# Protection_channel_C_Page_4.net
KiCad netlist of a schematic drawn in Altium Designer
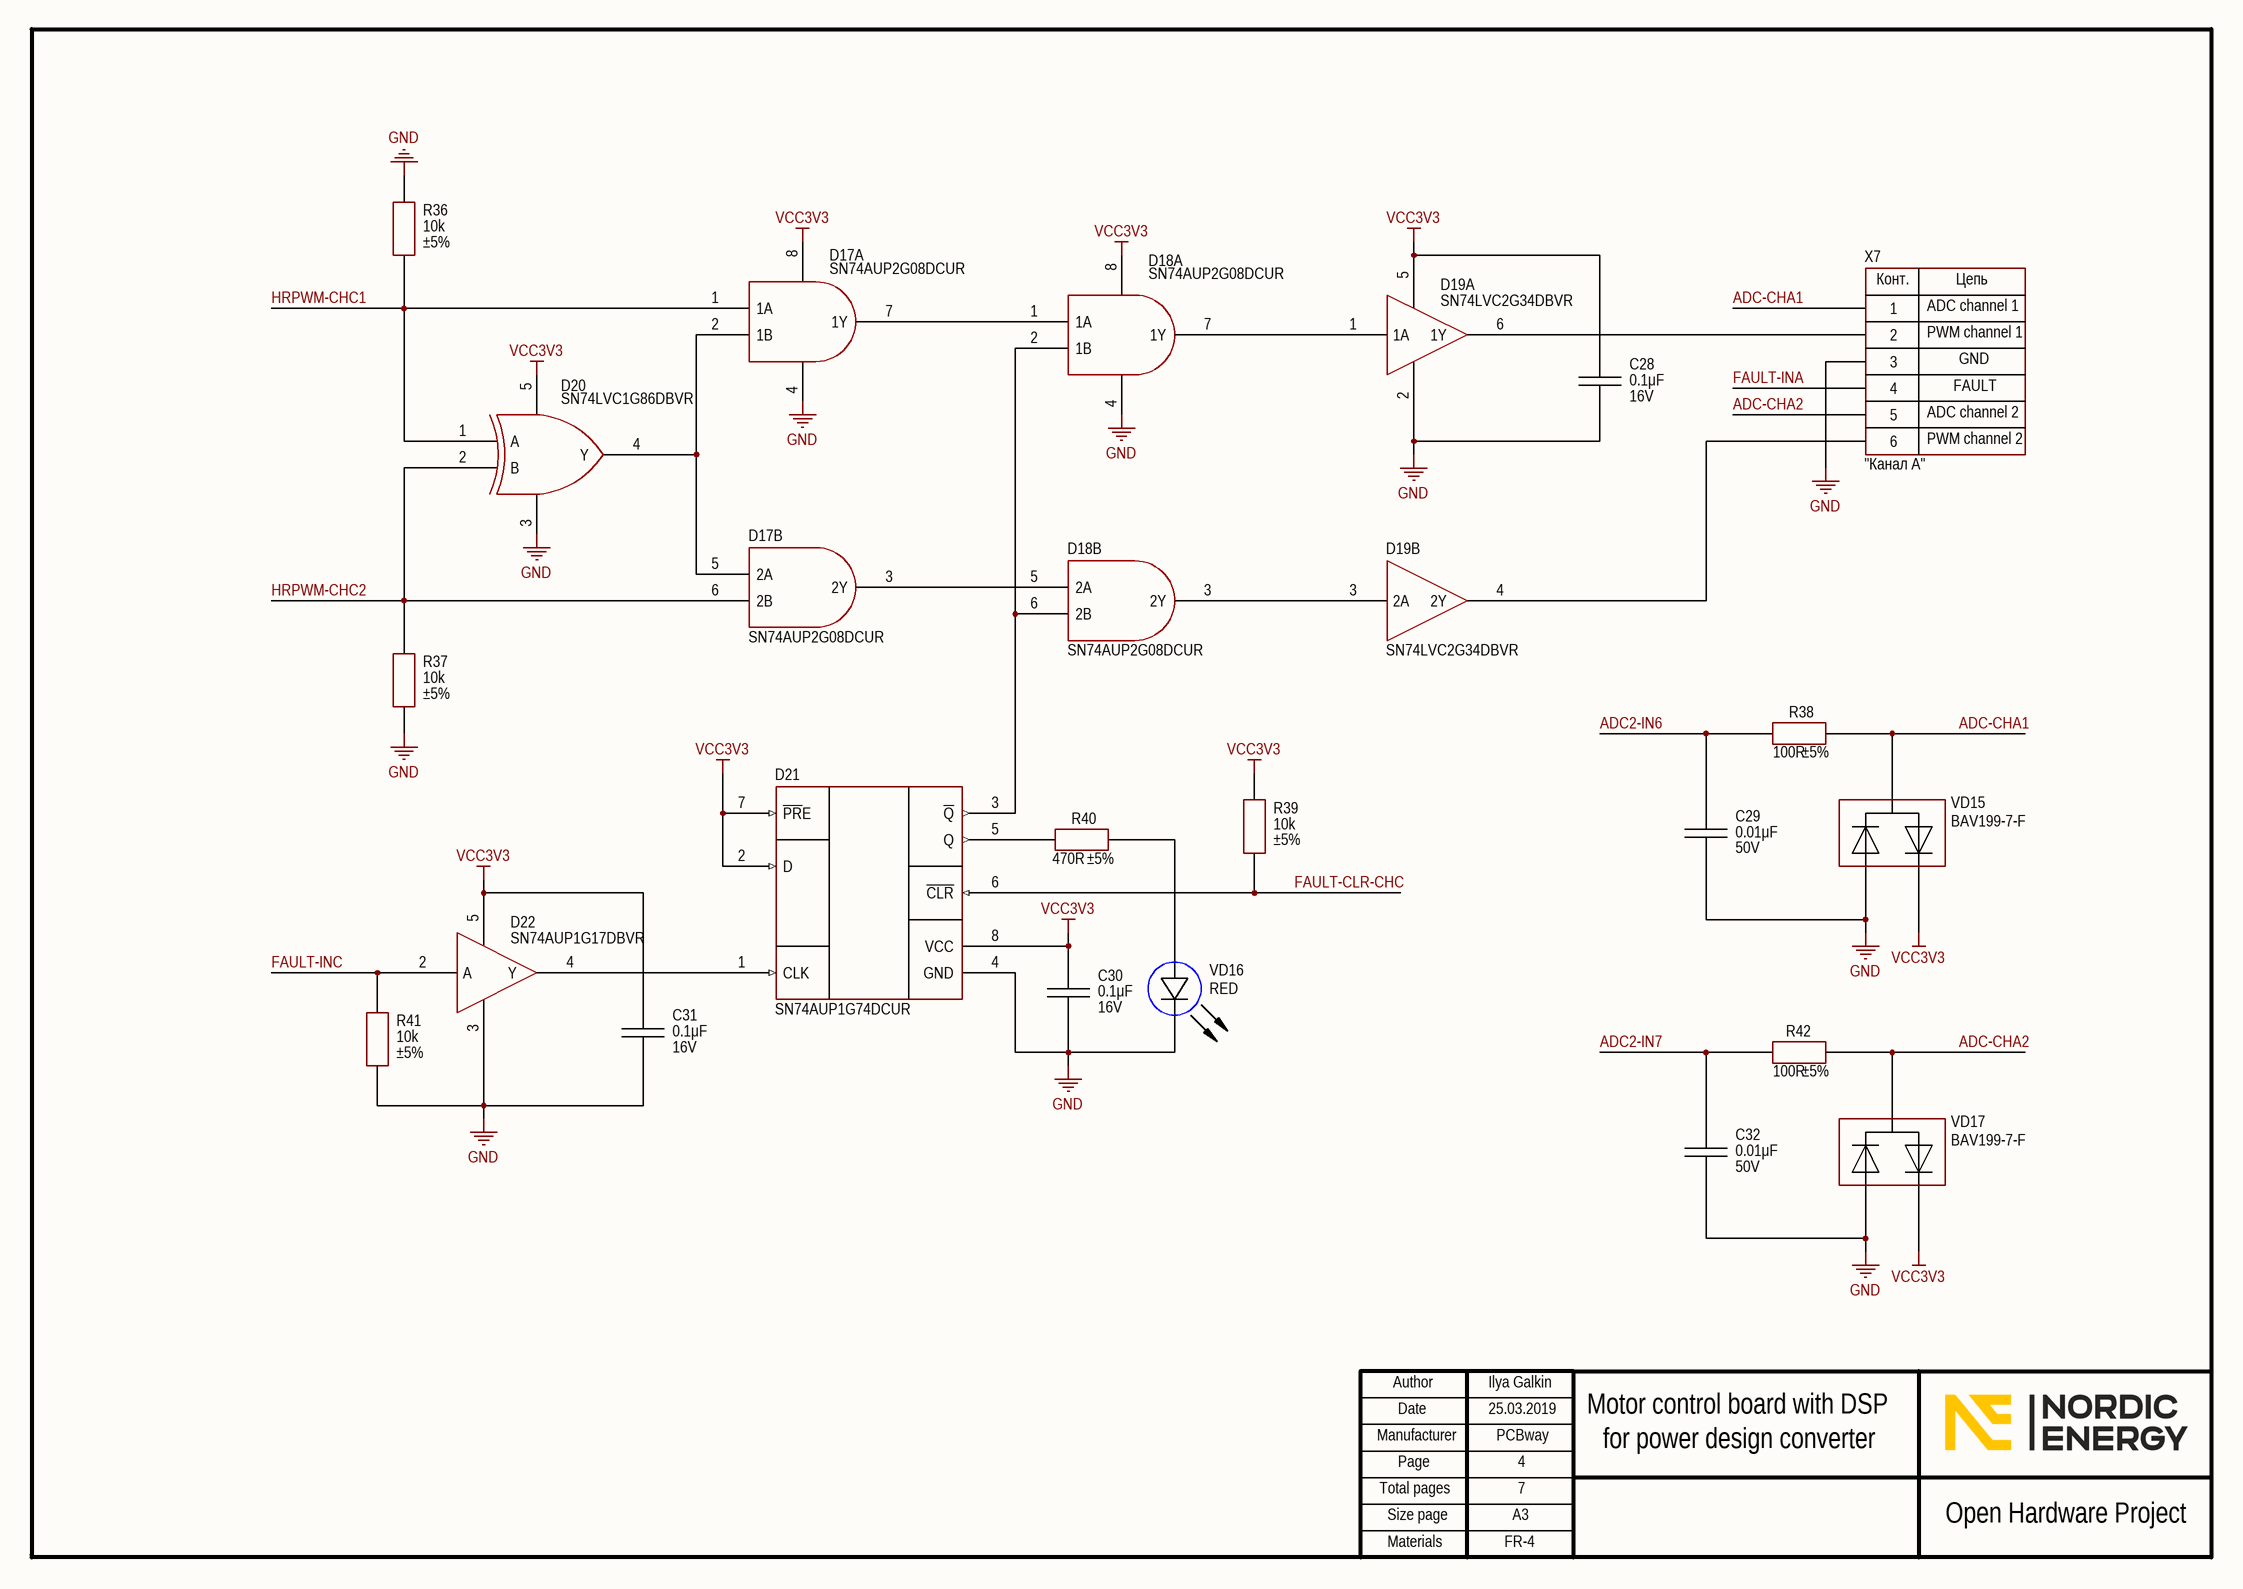
[diagram p0: Protection channel C. Page 4.SchDoc]

(export (version "E")
  (design (tool "Eeschema 10.0.6"))
  (components
    (comp (ref "C28")
      (value "0.1μF")
      (footprint "CAP: 0805")
      (fields
        (field (name "MANUFACTURER") "Yageo")
        (field (name "PARTNUMBER") "CC0805KRX7R7BB104")
        (field (name "VALUEMANUFACTURERPARTNUMBER") "Ceramic capacitor, 0.1μF, X7R, ±10%, 16V, 0805, -55...+125°C")
        (field (name "VOLTAGE") "16V")
      )
      (libsource (lib "Capacitor") (part "Ceramic_0805"))
    )
    (comp (ref "C29")
      (value "0.01μF")
      (footprint "CAP: 0805")
      (fields
        (field (name "MANUFACTURER") "Yageo")
        (field (name "PARTNUMBER") "CC0805KRX7R9BB103")
        (field (name "VALUEMANUFACTURERPARTNUMBER") "Ceramic capacitor, 0.01μF, X7R, ±10%, 50V, 0805, -55...+125°C")
        (field (name "VOLTAGE") "50V")
      )
      (libsource (lib "Capacitor") (part "Ceramic_0805"))
    )
    (comp (ref "C30")
      (value "0.1μF")
      (footprint "CAP: 0805")
      (fields
        (field (name "MANUFACTURER") "Yageo")
        (field (name "PARTNUMBER") "CC0805KRX7R7BB104")
        (field (name "VALUEMANUFACTURERPARTNUMBER") "Ceramic capacitor, 0.1μF, X7R, ±10%, 16V, 0805, -55...+125°C")
        (field (name "VOLTAGE") "16V")
      )
      (libsource (lib "Capacitor") (part "Ceramic_0805"))
    )
    (comp (ref "C31")
      (value "0.1μF")
      (footprint "CAP: 0805")
      (fields
        (field (name "MANUFACTURER") "Yageo")
        (field (name "PARTNUMBER") "CC0805KRX7R7BB104")
        (field (name "VALUEMANUFACTURERPARTNUMBER") "Ceramic capacitor, 0.1μF, X7R, ±10%, 16V, 0805, -55...+125°C")
        (field (name "VOLTAGE") "16V")
      )
      (libsource (lib "Capacitor") (part "Ceramic_0805"))
    )
    (comp (ref "C32")
      (value "0.01μF")
      (footprint "CAP: 0805")
      (fields
        (field (name "MANUFACTURER") "Yageo")
        (field (name "PARTNUMBER") "CC0805KRX7R9BB103")
        (field (name "VALUEMANUFACTURERPARTNUMBER") "Ceramic capacitor, 0.01μF, X7R, ±10%, 50V, 0805, -55...+125°C")
        (field (name "VOLTAGE") "50V")
      )
      (libsource (lib "Capacitor") (part "Ceramic_0805"))
    )
    (comp (ref "D17")
      (value "~")
      (footprint "8-VSSOP")
      (description "AND")
      (fields
        (field (name "MANUFACTURER") "Texas Instruments")
        (field (name "VALUEMANUFACTURERPARTNUMBER") "IC logic AND, 0.8...3.6V, -40...+855°C, 8-VSSOP")
        (field (name "PARTNUMBER") "SN74AUP2G08DCUR")
      )
      (libsource (lib "IC. Logic") (part "SN74AUP2G08DCUR"))
    )
    (comp (ref "D18")
      (value "~")
      (footprint "8-VSSOP")
      (description "AND")
      (fields
        (field (name "MANUFACTURER") "Texas Instruments")
        (field (name "VALUEMANUFACTURERPARTNUMBER") "IC logic AND, 0.8...3.6V, -40...+855°C, 8-VSSOP")
        (field (name "PARTNUMBER") "SN74AUP2G08DCUR")
      )
      (libsource (lib "IC. Logic") (part "SN74AUP2G08DCUR"))
    )
    (comp (ref "D19")
      (value "~")
      (footprint "SOT23-6")
      (description "Buffer")
      (fields
        (field (name "MANUFACTURER") "Texas Instruments")
        (field (name "VALUEMANUFACTURERPARTNUMBER") "IC logic buffer, 1.65...5.5V, -40...+125°C, SOT23-6")
        (field (name "PARTNUMBER") "SN74LVC2G34DBVR")
      )
      (libsource (lib "IC. Logic") (part "SN74LVC2G34DBVR"))
    )
    (comp (ref "D20")
      (value "~")
      (footprint "SOT23-5")
      (description "XOR")
      (fields
        (field (name "MANUFACTURER") "Texas Instruments")
        (field (name "VALUEMANUFACTURERPARTNUMBER") "IC logic XOR, 1.65...5.5V, -40...+125°C, SOT23-5")
        (field (name "PARTNUMBER") "SN74LVC1G86DBVR")
      )
      (libsource (lib "IC. Logic") (part "SN74LVC1G86DBVR"))
    )
    (comp (ref "D21")
      (value "~")
      (footprint "8-VSSOP")
      (description "D-trigger")
      (fields
        (field (name "MANUFACTURER") "Texas Instruments")
        (field (name "VALUEMANUFACTURERPARTNUMBER") "ICtrigger D-type, 0.8...3.6V, -40...+85°C, 8-VSSOP")
        (field (name "PARTNUMBER") "SN74AUP1G74DCUR")
      )
      (libsource (lib "IC. Logic") (part "SN74AUP1G74DCUR"))
    )
    (comp (ref "D22")
      (value "~")
      (footprint "SOT23-5")
      (description "Schmitt trigger")
      (fields
        (field (name "MANUFACTURER") "Texas Instruments")
        (field (name "VALUEMANUFACTURERPARTNUMBER") "IC Schmitt trigger, 0.8...3.6V, -40...+85°C, SOT23-6")
        (field (name "PARTNUMBER") "SN74AUP1G17DBVR")
      )
      (libsource (lib "IC. Logic") (part "SN74AUP1G17DBVR"))
    )
    (comp (ref "R36")
      (value "10k")
      (footprint "RES: 0805")
      (fields
        (field (name "MANUFACTURER") "Yageo")
        (field (name "PARTNUMBER") "RC0805JR-0710KL")
        (field (name "VALUEMANUFACTURERPARTNUMBER") "Resistor film, 10k, ±5%, 0805, 0.125W, -55...+125°C")
        (field (name "TOLERANCE") "±5%")
      )
      (libsource (lib "Resistor") (part "Resistor_0805"))
    )
    (comp (ref "R37")
      (value "10k")
      (footprint "RES: 0805")
      (fields
        (field (name "MANUFACTURER") "Yageo")
        (field (name "PARTNUMBER") "RC0805JR-0710KL")
        (field (name "VALUEMANUFACTURERPARTNUMBER") "Resistor film, 10k, ±5%, 0805, 0.125W, -55...+125°C")
        (field (name "TOLERANCE") "±5%")
      )
      (libsource (lib "Resistor") (part "Resistor_0805"))
    )
    (comp (ref "R38")
      (value "100R")
      (footprint "RES: 0805")
      (fields
        (field (name "MANUFACTURER") "Yageo")
        (field (name "PARTNUMBER") "RC0805JR-07100RL")
        (field (name "VALUEMANUFACTURERPARTNUMBER") "Resistor film, 100R, ±5%, 0805, 0.125W, -55...+125°C")
        (field (name "TOLERANCE") "±5%")
      )
      (libsource (lib "") (part "Resistor_0805_1"))
    )
    (comp (ref "R39")
      (value "10k")
      (footprint "RES: 0805")
      (fields
        (field (name "MANUFACTURER") "Yageo")
        (field (name "PARTNUMBER") "RC0805JR-0710KL")
        (field (name "VALUEMANUFACTURERPARTNUMBER") "Resistor film, 10k, ±5%, 0805, 0.125W, -55...+125°C")
        (field (name "TOLERANCE") "±5%")
      )
      (libsource (lib "Resistor") (part "Resistor_0805"))
    )
    (comp (ref "R40")
      (value "470R")
      (footprint "RES: 0805")
      (fields
        (field (name "MANUFACTURER") "Yageo")
        (field (name "PARTNUMBER") "RC0805JR-07470RL")
        (field (name "VALUEMANUFACTURERPARTNUMBER") "Resistor film, 470R, ±5%, 0805, 0.125W, -55...+125°C")
        (field (name "TOLERANCE") "±5%")
      )
      (libsource (lib "") (part "Resistor_0805_2"))
    )
    (comp (ref "R41")
      (value "10k")
      (footprint "RES: 0805")
      (fields
        (field (name "MANUFACTURER") "Yageo")
        (field (name "PARTNUMBER") "RC0805JR-0710KL")
        (field (name "VALUEMANUFACTURERPARTNUMBER") "Resistor film, 10k, ±5%, 0805, 0.125W, -55...+125°C")
        (field (name "TOLERANCE") "±5%")
      )
      (libsource (lib "Resistor") (part "Resistor_0805"))
    )
    (comp (ref "R42")
      (value "100R")
      (footprint "RES: 0805")
      (fields
        (field (name "MANUFACTURER") "Yageo")
        (field (name "PARTNUMBER") "RC0805JR-07100RL")
        (field (name "VALUEMANUFACTURERPARTNUMBER") "Resistor film, 100R, ±5%, 0805, 0.125W, -55...+125°C")
        (field (name "TOLERANCE") "±5%")
      )
      (libsource (lib "") (part "Resistor_0805_1"))
    )
    (comp (ref "VD15")
      (value "~")
      (footprint "SOT23")
      (fields
        (field (name "MANUFACTURER") "Diodes Incorporated")
        (field (name "VALUEMANUFACTURERPARTNUMBER") "Diode array, 85V, 140mA, 1.1V, 3us, SOT-23, -65...+150°C")
        (field (name "VOLTAGE") "85V")
        (field (name "PARTNUMBER") "BAV199-7-F")
      )
      (libsource (lib "Diode") (part "Diode_array"))
    )
    (comp (ref "VD16")
      (value "~")
      (footprint "LED: 0805R")
      (fields
        (field (name "MANUFACTURER") "Wurth")
        (field (name "VALUEMANUFACTURERPARTNUMBER") "LED, 20mA, 2V, 0805, -55...+150°C")
        (field (name "PARTNUMBER") "150080RS75000")
        (field (name "COLOR") "RED")
      )
      (libsource (lib "Diode") (part "LED_single"))
    )
    (comp (ref "VD17")
      (value "~")
      (footprint "SOT23")
      (fields
        (field (name "MANUFACTURER") "Diodes Incorporated")
        (field (name "VALUEMANUFACTURERPARTNUMBER") "Diode array, 85V, 140mA, 1.1V, 3us, SOT-23, -65...+150°C")
        (field (name "VOLTAGE") "85V")
        (field (name "PARTNUMBER") "BAV199-7-F")
      )
      (libsource (lib "Diode") (part "Diode_array"))
    )
    (comp (ref "X7")
      (value "~")
      (footprint "CON: PLD-6")
      (fields
        (field (name "MANUFACTURER") "Connfly")
        (field (name "VALUEMANUFACTURERPARTNUMBER") "Connector, 6pin, 2.54mm, 500VAC, 3A")
        (field (name "PARTNUMBER") "PLD-6")
        (field (name "COMMENTTEXT") "\"Канал А\"")
      )
      (libsource (lib "Connector") (part "PLD-6"))
    )
  )
  (nets
    (net (code "1") (name "/ADC-CHA1") (class "Default")
      (node (ref "R38") (pin "2") (pinfunction "2_2") (pintype "passive"))
      (node (ref "VD15") (pin "3") (pinfunction "3_3") (pintype "passive"))
      (node (ref "X7") (pin "1") (pinfunction "1_1") (pintype "passive"))
    )
    (net (code "2") (name "/ADC-CHA2") (class "Default")
      (node (ref "R42") (pin "2") (pinfunction "2_2") (pintype "passive"))
      (node (ref "VD17") (pin "3") (pinfunction "3_3") (pintype "passive"))
      (node (ref "X7") (pin "5") (pinfunction "5_5") (pintype "power_in"))
    )
    (net (code "3") (name "/ADC2-IN6") (class "Default")
      (node (ref "C29") (pin "2") (pinfunction "2_2") (pintype "power_in"))
      (node (ref "R38") (pin "1") (pinfunction "1_1") (pintype "passive"))
    )
    (net (code "4") (name "/ADC2-IN7") (class "Default")
      (node (ref "C32") (pin "2") (pinfunction "2_2") (pintype "power_in"))
      (node (ref "R42") (pin "1") (pinfunction "1_1") (pintype "passive"))
    )
    (net (code "5") (name "/FAULT-CLR-CHC") (class "Default")
      (node (ref "D21") (pin "6") (pinfunction "~{CLR}_6") (pintype "input"))
      (node (ref "R39") (pin "2") (pinfunction "2_2") (pintype "passive"))
    )
    (net (code "6") (name "/FAULT-INA") (class "Default")
      (node (ref "X7") (pin "4") (pinfunction "4_4") (pintype "power_in"))
    )
    (net (code "7") (name "/FAULT-INC") (class "Default")
      (node (ref "D22") (pin "2") (pinfunction "A_2") (pintype "passive"))
      (node (ref "R41") (pin "1") (pinfunction "1_1") (pintype "passive"))
    )
    (net (code "8") (name "/HRPWM-CHC1") (class "Default")
      (node (ref "D17") (pin "1") (pinfunction "1A_1") (pintype "passive"))
      (node (ref "D20") (pin "1") (pinfunction "A_1") (pintype "passive"))
      (node (ref "R36") (pin "2") (pinfunction "2_2") (pintype "passive"))
    )
    (net (code "9") (name "/HRPWM-CHC2") (class "Default")
      (node (ref "D17") (pin "6") (pinfunction "2B_6") (pintype "passive"))
      (node (ref "D20") (pin "2") (pinfunction "B_2") (pintype "passive"))
      (node (ref "R37") (pin "1") (pinfunction "1_1") (pintype "passive"))
    )
    (net (code "10") (name "GND") (class "Default")
      (node (ref "C28") (pin "1") (pinfunction "1_1") (pintype "power_in"))
      (node (ref "C29") (pin "1") (pinfunction "1_1") (pintype "power_in"))
      (node (ref "C30") (pin "1") (pinfunction "1_1") (pintype "power_in"))
      (node (ref "C31") (pin "1") (pinfunction "1_1") (pintype "power_in"))
      (node (ref "C32") (pin "1") (pinfunction "1_1") (pintype "power_in"))
      (node (ref "D17") (pin "4") (pintype "passive"))
      (node (ref "D18") (pin "4") (pintype "passive"))
      (node (ref "D19") (pin "2") (pintype "passive"))
      (node (ref "D20") (pin "3") (pintype "passive"))
      (node (ref "D21") (pin "4") (pinfunction "GND_4") (pintype "passive"))
      (node (ref "D22") (pin "3") (pintype "passive"))
      (node (ref "R36") (pin "1") (pinfunction "1_1") (pintype "passive"))
      (node (ref "R37") (pin "2") (pinfunction "2_2") (pintype "passive"))
      (node (ref "R41") (pin "2") (pinfunction "2_2") (pintype "passive"))
      (node (ref "VD15") (pin "1") (pinfunction "1_1") (pintype "passive"))
      (node (ref "VD16") (pin "2") (pinfunction "C_2") (pintype "passive"))
      (node (ref "VD17") (pin "1") (pinfunction "1_1") (pintype "passive"))
      (node (ref "X7") (pin "3") (pinfunction "3_3") (pintype "power_in"))
    )
    (net (code "11") (name "Net-(D17A-1B)") (class "Default")
      (node (ref "D17") (pin "2") (pinfunction "1B_2") (pintype "passive"))
      (node (ref "D17") (pin "5") (pinfunction "2A_5") (pintype "passive"))
      (node (ref "D20") (pin "4") (pinfunction "Y_4") (pintype "passive"))
    )
    (net (code "12") (name "Net-(D17A-1Y)") (class "Default")
      (node (ref "D17") (pin "7") (pinfunction "1Y_7") (pintype "passive"))
      (node (ref "D18") (pin "1") (pinfunction "1A_1") (pintype "passive"))
    )
    (net (code "13") (name "Net-(D17B-2Y)") (class "Default")
      (node (ref "D17") (pin "3") (pinfunction "2Y_3") (pintype "passive"))
      (node (ref "D18") (pin "5") (pinfunction "2A_5") (pintype "passive"))
    )
    (net (code "14") (name "Net-(D18A-1B)") (class "Default")
      (node (ref "D18") (pin "2") (pinfunction "1B_2") (pintype "passive"))
      (node (ref "D18") (pin "6") (pinfunction "2B_6") (pintype "passive"))
      (node (ref "D21") (pin "3") (pinfunction "~{Q}_3") (pintype "output"))
    )
    (net (code "15") (name "Net-(D18A-1Y)") (class "Default")
      (node (ref "D18") (pin "7") (pinfunction "1Y_7") (pintype "passive"))
      (node (ref "D19") (pin "1") (pinfunction "1A_1") (pintype "passive"))
    )
    (net (code "16") (name "Net-(D18B-2Y)") (class "Default")
      (node (ref "D18") (pin "3") (pinfunction "2Y_3") (pintype "passive"))
      (node (ref "D19") (pin "3") (pinfunction "2A_3") (pintype "passive"))
    )
    (net (code "17") (name "Net-(D19A-1Y)") (class "Default")
      (node (ref "D19") (pin "6") (pinfunction "1Y_6") (pintype "passive"))
      (node (ref "X7") (pin "2") (pinfunction "2_2") (pintype "passive"))
    )
    (net (code "18") (name "Net-(D19B-2Y)") (class "Default")
      (node (ref "D19") (pin "4") (pinfunction "2Y_4") (pintype "passive"))
      (node (ref "X7") (pin "6") (pinfunction "6_6") (pintype "power_in"))
    )
    (net (code "19") (name "Net-(D21-CLK)") (class "Default")
      (node (ref "D21") (pin "1") (pinfunction "CLK_1") (pintype "input"))
      (node (ref "D22") (pin "4") (pinfunction "Y_4") (pintype "passive"))
    )
    (net (code "20") (name "Net-(D21-Q)") (class "Default")
      (node (ref "D21") (pin "5") (pinfunction "Q_5") (pintype "output"))
      (node (ref "R40") (pin "2") (pinfunction "2_2") (pintype "passive"))
    )
    (net (code "21") (name "Net-(VD16-A)") (class "Default")
      (node (ref "R40") (pin "1") (pinfunction "1_1") (pintype "passive"))
      (node (ref "VD16") (pin "1") (pinfunction "A_1") (pintype "passive"))
    )
    (net (code "22") (name "VCC3V3") (class "Default")
      (node (ref "C28") (pin "2") (pinfunction "2_2") (pintype "power_in"))
      (node (ref "C30") (pin "2") (pinfunction "2_2") (pintype "power_in"))
      (node (ref "C31") (pin "2") (pinfunction "2_2") (pintype "power_in"))
      (node (ref "D17") (pin "8") (pintype "passive"))
      (node (ref "D18") (pin "8") (pintype "passive"))
      (node (ref "D19") (pin "5") (pintype "passive"))
      (node (ref "D20") (pin "5") (pintype "passive"))
      (node (ref "D21") (pin "2") (pinfunction "D_2") (pintype "input"))
      (node (ref "D21") (pin "7") (pinfunction "~{PR}E_7") (pintype "input"))
      (node (ref "D21") (pin "8") (pinfunction "VCC_8") (pintype "passive"))
      (node (ref "D22") (pin "5") (pintype "passive"))
      (node (ref "R39") (pin "1") (pinfunction "1_1") (pintype "passive"))
      (node (ref "VD15") (pin "2") (pinfunction "2_2") (pintype "passive"))
      (node (ref "VD17") (pin "2") (pinfunction "2_2") (pintype "passive"))
    )
  )
)
